# Bosch.net
KiCad netlist of a schematic drawn in Altium Designer
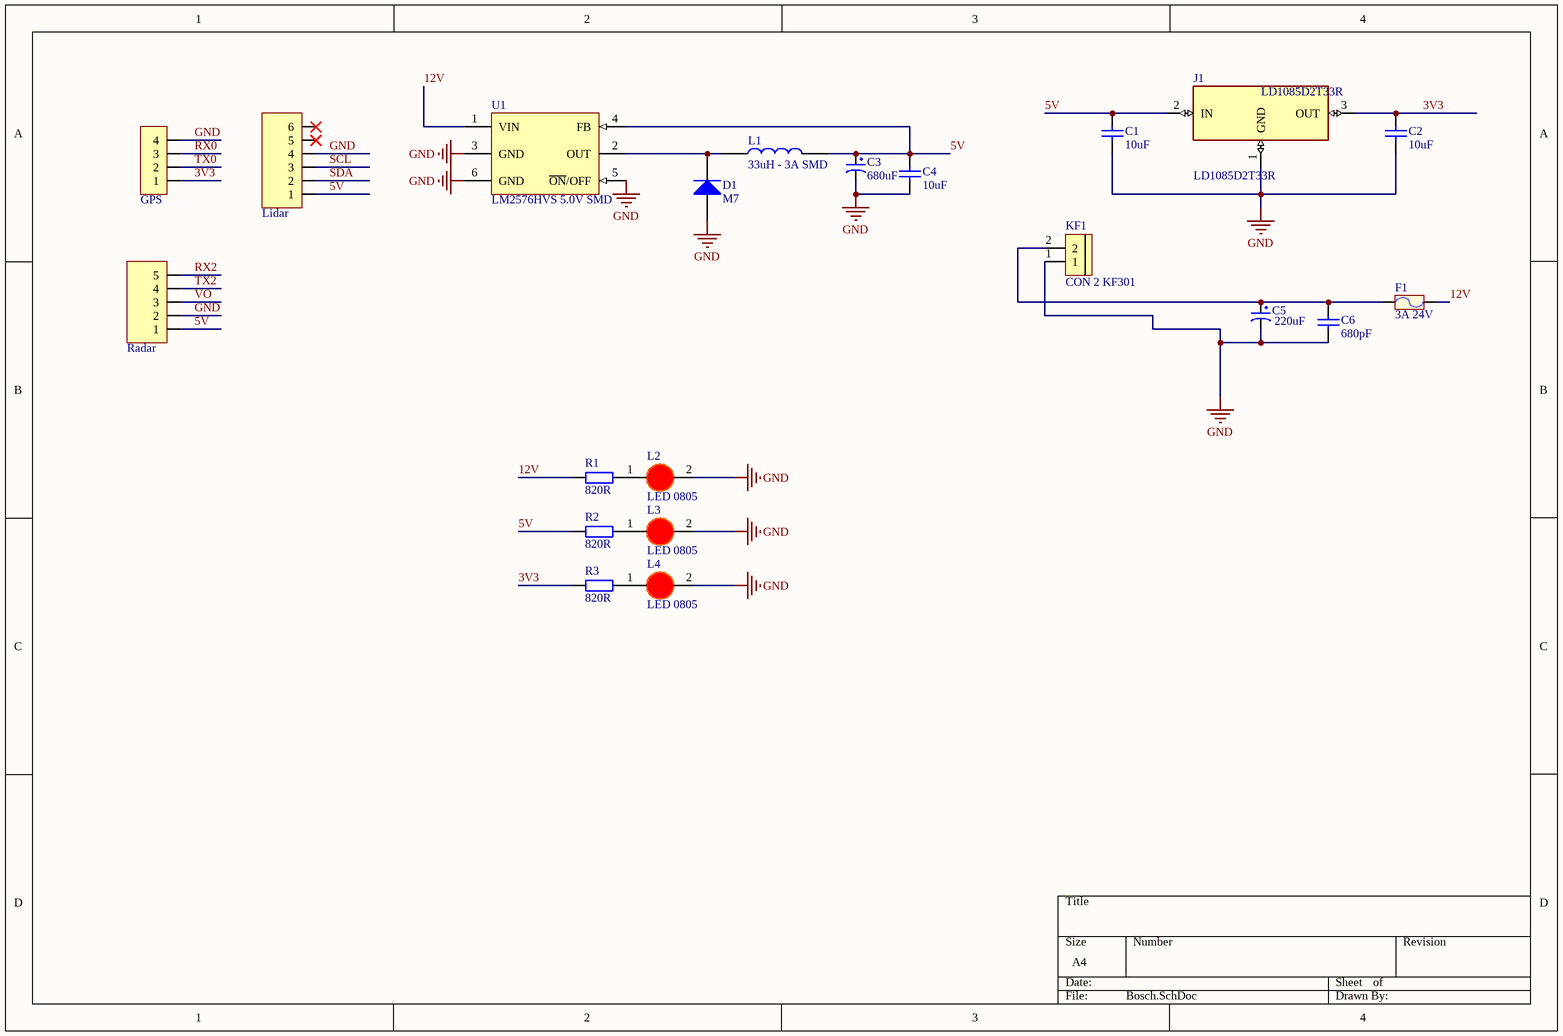
[diagram p0: Bosch.SchDoc]

(export (version "E")
  (design (tool "Eeschema 10.0.6"))
  (components
    (comp (ref "C1")
      (value "10uF")
      (footprint "tu 0805")
      (description "Dán")
      (libsource (lib "Altium_Lib_by_KhueNguyenCreator") (part "Tu 0805 680pF 50V 10%"))
    )
    (comp (ref "C2")
      (value "10uF")
      (footprint "tu 0805")
      (description "Dán")
      (libsource (lib "Altium_Lib_by_KhueNguyenCreator") (part "Tu 0805 680pF 50V 10%"))
    )
    (comp (ref "C3")
      (value "680uF")
      (footprint "tu hoa 10mm")
      (description "Cắm")
      (libsource (lib "Altium_Lib_by_KhueNguyenCreator") (part "Tu Hoa 470uF 35V 10x15"))
    )
    (comp (ref "C4")
      (value "10uF")
      (footprint "tu 0805")
      (description "Dán")
      (libsource (lib "Altium_Lib_by_KhueNguyenCreator") (part "Tu 0805 680pF 50V 10%"))
    )
    (comp (ref "C5")
      (value "220uF")
      (footprint "tu hoa 10mm")
      (description "Cắm")
      (libsource (lib "Altium_Lib_by_KhueNguyenCreator") (part "Tu Hoa 470uF 35V 10x15"))
    )
    (comp (ref "C6")
      (value "680pF")
      (footprint "tu 0805")
      (description "Dán")
      (libsource (lib "Altium_Lib_by_KhueNguyenCreator") (part "Tu 0805 680pF 50V 10%"))
    )
    (comp (ref "D1")
      (value "M7")
      (footprint "DIODE SMA")
      (description "Dán")
      (libsource (lib "Altium_Lib_by_KhueNguyenCreator") (part "Diode M7 ( 4007 )"))
    )
    (comp (ref "F1")
      (value "3A 24V")
      (footprint "Cau chi tu phuc hoi 2A 24V SMD1812")
      (description "2A 24V SMD1812")
      (libsource (lib "Altium_Lib_by_KhueNguyenCreator") (part "Cau chi tu phuc hoi 2A 24V SMD1812"))
    )
    (comp (ref "J1")
      (value "LD1085D2T33R")
      (footprint "LD1085D2T33R")
      (description "Linear Voltage Regulator IC Positive Fixed 1 Output 3A D2PAK")
      (fields (field (name "MF") "STMicroelectronics"))
      (libsource (lib "LD1085D2T33R") (part "LD1085D2T33R"))
    )
    (comp (ref "JP1")
      (value "Radar")
      (footprint "JP 1x5 CT")
      (description "Cắm")
      (libsource (lib "Altium_Lib_by_KhueNguyenCreator") (part "JP 1x5 2.54 Cai Thang"))
    )
    (comp (ref "JP2")
      (value "Lidar")
      (footprint "JP 1x6 CT")
      (description "Cắm")
      (libsource (lib "Altium_Lib_by_KhueNguyenCreator") (part "JP 1x6 2.54 Cai Thang"))
    )
    (comp (ref "JP3")
      (value "GPS")
      (footprint "JP 1x4 CT")
      (description "Cắm")
      (libsource (lib "Altium_Lib_by_KhueNguyenCreator") (part "JP 1x4 2.54 Cai Thang"))
    )
    (comp (ref "KF1")
      (value "CON 2 KF301")
      (footprint "Con 2 KF301 5.08")
      (description "Cắm")
      (libsource (lib "Altium_Lib_by_KhueNguyenCreator") (part "CON 2 KF301"))
    )
    (comp (ref "L1")
      (value "33uH - 3A SMD")
      (footprint "Cuon Cam 12x12x10")
      (description "Dán")
      (libsource (lib "Altium_Lib_by_KhueNguyenCreator") (part "CUON CAM 100uH SMD"))
    )
    (comp (ref "L2")
      (value "LED 0805")
      (footprint "LED-0805-Red")
      (description "Dán")
      (libsource (lib "Altium_Lib_by_KhueNguyenCreator") (part "LED 0805 Do"))
    )
    (comp (ref "L3")
      (value "LED 0805")
      (footprint "LED-0805-Red")
      (description "Dán")
      (libsource (lib "Altium_Lib_by_KhueNguyenCreator") (part "LED 0805 Do"))
    )
    (comp (ref "L4")
      (value "LED 0805")
      (footprint "LED-0805-Red")
      (description "Dán")
      (libsource (lib "Altium_Lib_by_KhueNguyenCreator") (part "LED 0805 Do"))
    )
    (comp (ref "R1")
      (value "820R")
      (footprint "Tro SMD 0805")
      (description "Dán")
      (libsource (lib "Altium_Lib_by_KhueNguyenCreator") (part "Tro 0805 5% 820R"))
    )
    (comp (ref "R2")
      (value "820R")
      (footprint "Tro SMD 0805")
      (description "Dán")
      (libsource (lib "Altium_Lib_by_KhueNguyenCreator") (part "Tro 0805 5% 820R"))
    )
    (comp (ref "R3")
      (value "820R")
      (footprint "Tro SMD 0805")
      (description "Dán")
      (libsource (lib "Altium_Lib_by_KhueNguyenCreator") (part "Tro 0805 5% 820R"))
    )
    (comp (ref "U1")
      (value "LM2576HVS 5.0V SMD")
      (footprint "TO263-5")
      (description "Dán")
      (libsource (lib "Altium_Lib_by_KhueNguyenCreator") (part "LM2576HVS 5.0V SMD"))
    )
  )
  (nets
    (net (code "1") (name "/3V3") (class "Default")
      (node (ref "C2") (pin "1") (pinfunction "1_1") (pintype "passive"))
      (node (ref "J1") (pin "3") (pinfunction "OUT_3") (pintype "bidirectional"))
      (node (ref "JP3") (pin "1") (pinfunction "1_1") (pintype "passive"))
      (node (ref "R3") (pin "1") (pinfunction "1_1") (pintype "passive"))
    )
    (net (code "2") (name "/5V") (class "Default")
      (node (ref "C1") (pin "1") (pinfunction "1_1") (pintype "passive"))
      (node (ref "C3") (pin "1") (pinfunction "1_1") (pintype "passive"))
      (node (ref "C4") (pin "1") (pinfunction "1_1") (pintype "passive"))
      (node (ref "J1") (pin "2") (pinfunction "IN_2") (pintype "bidirectional"))
      (node (ref "JP1") (pin "1") (pinfunction "1_1") (pintype "passive"))
      (node (ref "JP2") (pin "1") (pinfunction "1_1") (pintype "passive"))
      (node (ref "L1") (pin "2") (pinfunction "2_2") (pintype "passive"))
      (node (ref "R2") (pin "1") (pinfunction "1_1") (pintype "passive"))
      (node (ref "U1") (pin "4") (pinfunction "FB_4") (pintype "input"))
    )
    (net (code "3") (name "/12V") (class "Default")
      (node (ref "F1") (pin "2") (pinfunction "2_2") (pintype "passive"))
      (node (ref "R1") (pin "1") (pinfunction "1_1") (pintype "passive"))
      (node (ref "U1") (pin "1") (pinfunction "VIN_1") (pintype "power_in"))
    )
    (net (code "4") (name "/RX0") (class "Default")
      (node (ref "JP3") (pin "3") (pinfunction "3_3") (pintype "passive"))
    )
    (net (code "5") (name "/RX2") (class "Default")
      (node (ref "JP1") (pin "5") (pinfunction "5_5") (pintype "passive"))
    )
    (net (code "6") (name "/SCL") (class "Default")
      (node (ref "JP2") (pin "3") (pinfunction "3_3") (pintype "passive"))
    )
    (net (code "7") (name "/SDA") (class "Default")
      (node (ref "JP2") (pin "2") (pinfunction "2_2") (pintype "passive"))
    )
    (net (code "8") (name "/TX0") (class "Default")
      (node (ref "JP3") (pin "2") (pinfunction "2_2") (pintype "passive"))
    )
    (net (code "9") (name "/TX2") (class "Default")
      (node (ref "JP1") (pin "4") (pinfunction "4_4") (pintype "passive"))
    )
    (net (code "10") (name "/VO") (class "Default")
      (node (ref "JP1") (pin "3") (pinfunction "3_3") (pintype "passive"))
    )
    (net (code "11") (name "GND") (class "Default")
      (node (ref "C1") (pin "2") (pinfunction "2_2") (pintype "passive"))
      (node (ref "C2") (pin "2") (pinfunction "2_2") (pintype "passive"))
      (node (ref "C3") (pin "2") (pinfunction "2_2") (pintype "passive"))
      (node (ref "C4") (pin "2") (pinfunction "2_2") (pintype "passive"))
      (node (ref "C5") (pin "2") (pinfunction "2_2") (pintype "passive"))
      (node (ref "C6") (pin "2") (pinfunction "2_2") (pintype "passive"))
      (node (ref "D1") (pin "1") (pinfunction "A_1") (pintype "passive"))
      (node (ref "J1") (pin "1") (pinfunction "GND_1") (pintype "bidirectional"))
      (node (ref "JP1") (pin "2") (pinfunction "2_2") (pintype "passive"))
      (node (ref "JP2") (pin "4") (pinfunction "4_4") (pintype "passive"))
      (node (ref "JP3") (pin "4") (pinfunction "4_4") (pintype "passive"))
      (node (ref "KF1") (pin "1") (pinfunction "1_1") (pintype "passive"))
      (node (ref "L2") (pin "2") (pinfunction "K_2") (pintype "passive"))
      (node (ref "L3") (pin "2") (pinfunction "K_2") (pintype "passive"))
      (node (ref "L4") (pin "2") (pinfunction "K_2") (pintype "passive"))
      (node (ref "U1") (pin "3") (pinfunction "GND_3") (pintype "power_in"))
      (node (ref "U1") (pin "5") (pinfunction "~{ON}/OFF_5") (pintype "input"))
      (node (ref "U1") (pin "6") (pinfunction "GND_6") (pintype "passive"))
    )
    (net (code "12") (name "Net-(C5-Pad1)") (class "Default")
      (node (ref "C5") (pin "1") (pinfunction "1_1") (pintype "passive"))
      (node (ref "C6") (pin "1") (pinfunction "1_1") (pintype "passive"))
      (node (ref "F1") (pin "1") (pinfunction "1_1") (pintype "passive"))
      (node (ref "KF1") (pin "2") (pinfunction "2_2") (pintype "passive"))
    )
    (net (code "13") (name "Net-(D1-K)") (class "Default")
      (node (ref "D1") (pin "2") (pinfunction "K_2") (pintype "passive"))
      (node (ref "L1") (pin "1") (pinfunction "1_1") (pintype "passive"))
      (node (ref "U1") (pin "2") (pinfunction "OUT_2") (pintype "power_in"))
    )
    (net (code "14") (name "Net-(L2-A)") (class "Default")
      (node (ref "L2") (pin "1") (pinfunction "A_1") (pintype "passive"))
      (node (ref "R1") (pin "2") (pinfunction "2_2") (pintype "passive"))
    )
    (net (code "15") (name "Net-(L3-A)") (class "Default")
      (node (ref "L3") (pin "1") (pinfunction "A_1") (pintype "passive"))
      (node (ref "R2") (pin "2") (pinfunction "2_2") (pintype "passive"))
    )
    (net (code "16") (name "Net-(L4-A)") (class "Default")
      (node (ref "L4") (pin "1") (pinfunction "A_1") (pintype "passive"))
      (node (ref "R3") (pin "2") (pinfunction "2_2") (pintype "passive"))
    )
    (net (code "17") (name "unconnected-(JP2-Pad5)") (class "Default")
      (node (ref "JP2") (pin "5") (pinfunction "5_5") (pintype "passive+no_connect"))
    )
    (net (code "18") (name "unconnected-(JP2-Pad6)") (class "Default")
      (node (ref "JP2") (pin "6") (pinfunction "6_6") (pintype "passive+no_connect"))
    )
  )
)
